# TwinSensorRevC.net
KiCad netlist of a schematic drawn in EAGLE
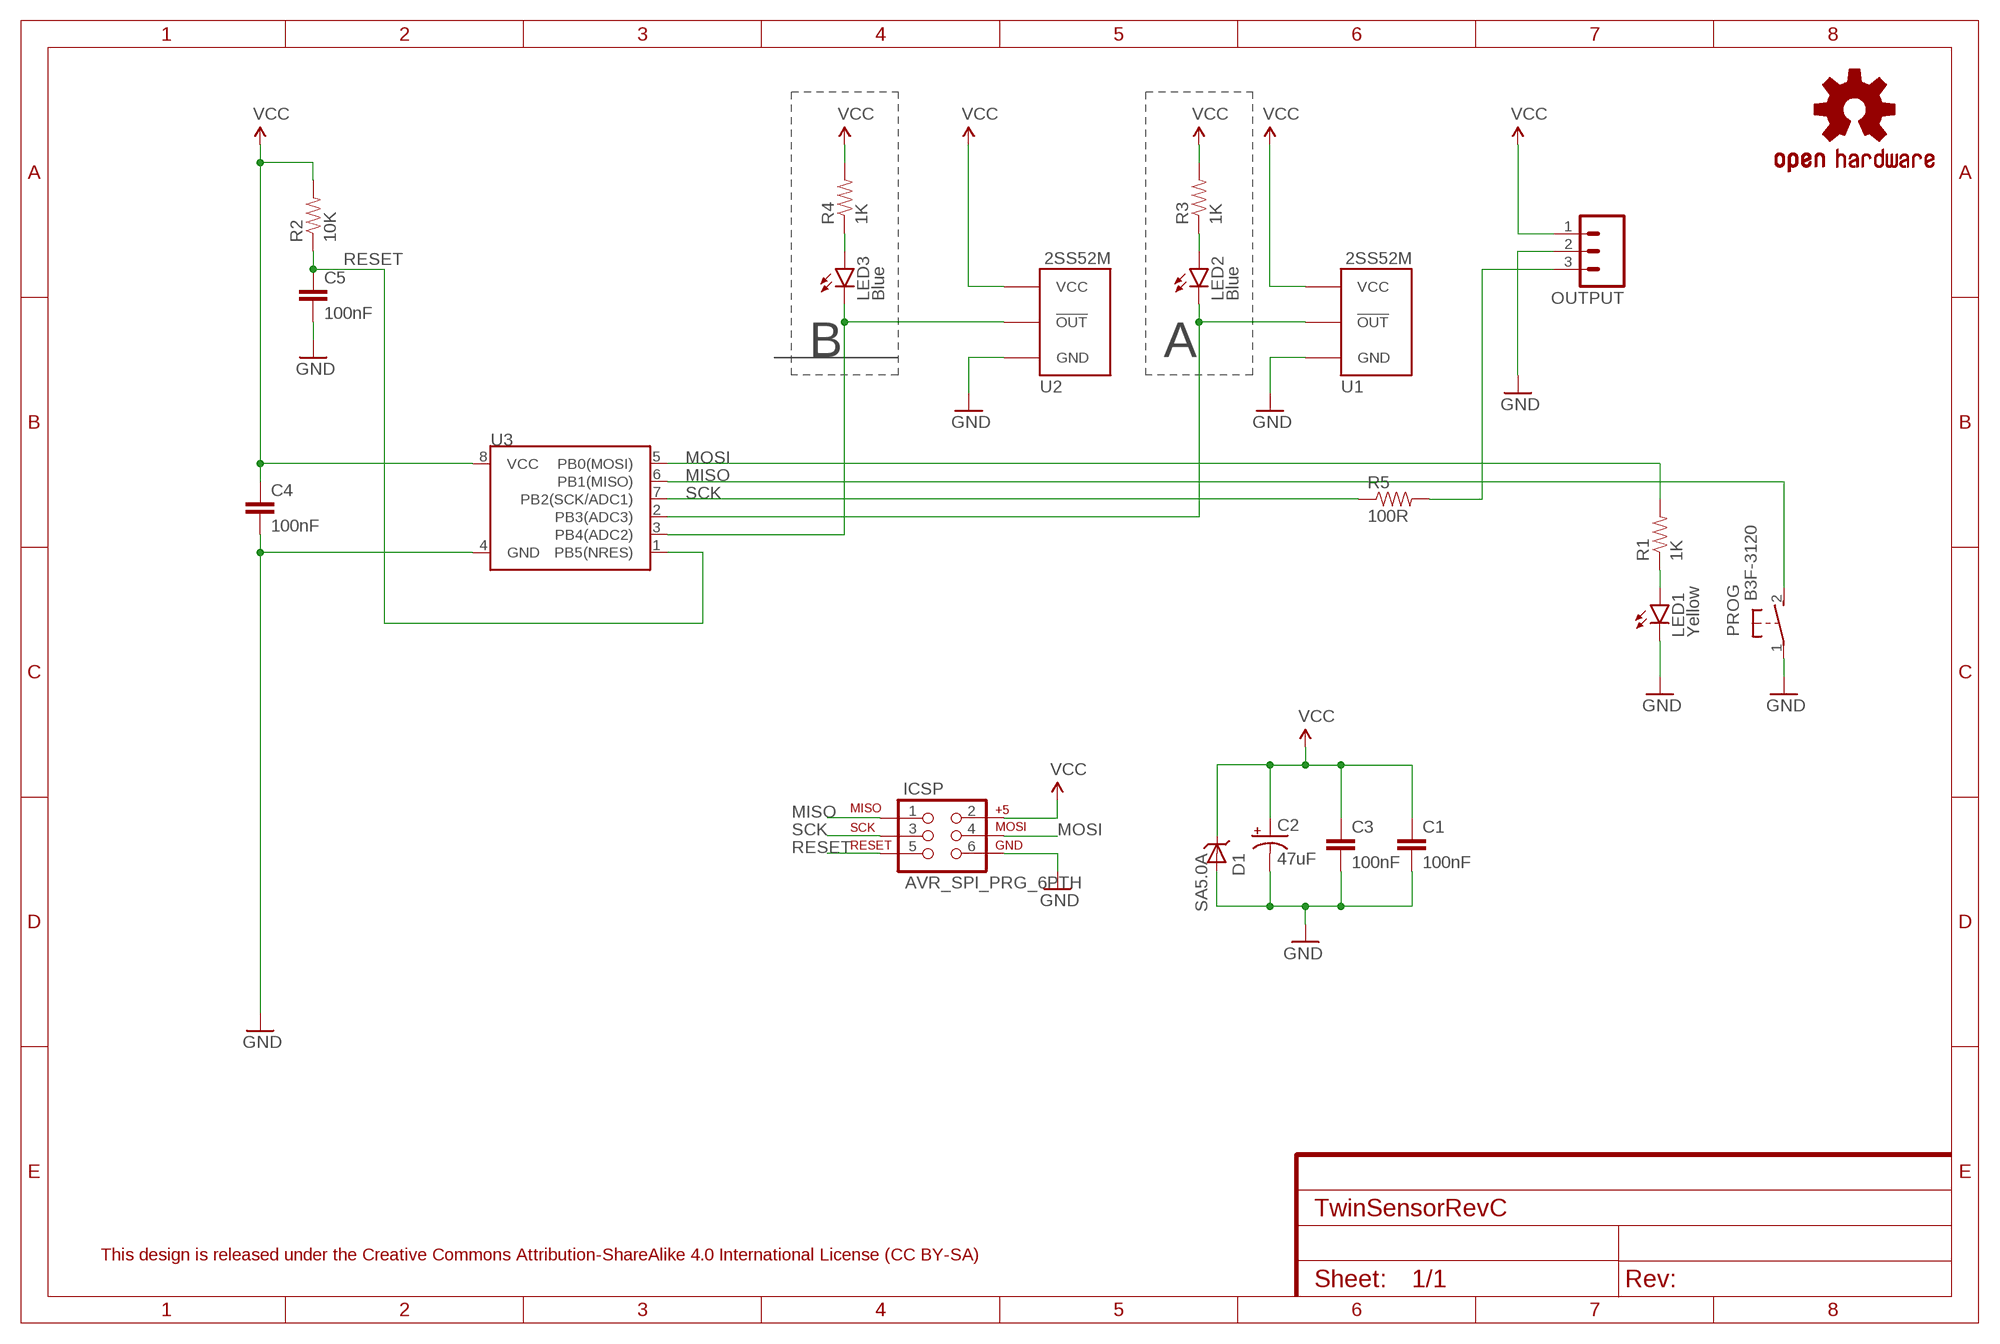
[diagram p0: schematic, sheet 1]

(export (version "E")
  (design (tool "Eeschema 10.0.6"))
  (components
    (comp (ref "C1")
      (value "100nF")
      (footprint "eagle-import:CAP-PTH-SMALL")
      (libsource (lib "eagle-import") (part "CAPPTH"))
    )
    (comp (ref "C2")
      (value "47uF")
      (footprint "eagle-import:CPOL-RADIAL-100UF-25V")
      (libsource (lib "eagle-import") (part "CAP_POLPTH1"))
    )
    (comp (ref "C3")
      (value "100nF")
      (footprint "eagle-import:CAP-PTH-SMALL")
      (libsource (lib "eagle-import") (part "CAPPTH"))
    )
    (comp (ref "C4")
      (value "100nF")
      (footprint "eagle-import:CAP-PTH-SMALL")
      (libsource (lib "eagle-import") (part "CAPPTH"))
    )
    (comp (ref "C5")
      (value "100nF")
      (footprint "eagle-import:CAP-PTH-SMALL")
      (libsource (lib "eagle-import") (part "CAPPTH"))
    )
    (comp (ref "D1")
      (value "SA5.0A")
      (footprint "eagle-import:DO41_TVS_UNI")
      (libsource (lib "eagle-import") (part "SA5.0A"))
    )
    (comp (ref "ICSP")
      (value "AVR_SPI_PRG_6PTH")
      (footprint "eagle-import:2X3")
      (libsource (lib "eagle-import") (part "AVR_SPI_PRG_6PTH"))
    )
    (comp (ref "LED1")
      (value "Yellow")
      (footprint "eagle-import:LED3MM")
      (libsource (lib "eagle-import") (part "LED3MM"))
    )
    (comp (ref "LED2")
      (value "Blue")
      (footprint "eagle-import:LED3MM")
      (libsource (lib "eagle-import") (part "LED3MM"))
    )
    (comp (ref "LED3")
      (value "Blue")
      (footprint "eagle-import:LED3MM")
      (libsource (lib "eagle-import") (part "LED3MM"))
    )
    (comp (ref "LOGO1")
      (value "OSHW-LOGOS")
      (footprint "eagle-import:OSHW-LOGO-S")
      (libsource (lib "eagle-import") (part "OSHW-LOGOS"))
    )
    (comp (ref "OUTPUT")
      (value "M03PTH")
      (footprint "eagle-import:1X03")
      (libsource (lib "eagle-import") (part "M03PTH"))
    )
    (comp (ref "PROG")
      (value "B3F-3120")
      (footprint "eagle-import:B3F-3120")
      (fields (field (name "MPN") "B3F-3100"))
      (libsource (lib "eagle-import") (part "B3F-3120"))
    )
    (comp (ref "R1")
      (value "1K")
      (footprint "eagle-import:AXIAL-0.4")
      (libsource (lib "eagle-import") (part "RESISTORPTH-1/4W"))
    )
    (comp (ref "R2")
      (value "10K")
      (footprint "eagle-import:AXIAL-0.4")
      (libsource (lib "eagle-import") (part "RESISTORPTH-1/4W"))
    )
    (comp (ref "R3")
      (value "1K")
      (footprint "eagle-import:AXIAL-0.4")
      (libsource (lib "eagle-import") (part "RESISTORPTH-1/4W"))
    )
    (comp (ref "R4")
      (value "1K")
      (footprint "eagle-import:AXIAL-0.4")
      (libsource (lib "eagle-import") (part "RESISTORPTH-1/4W"))
    )
    (comp (ref "R5")
      (value "100R")
      (footprint "eagle-import:AXIAL-0.4")
      (libsource (lib "eagle-import") (part "RESISTORPTH-1/4W"))
    )
    (comp (ref "U1")
      (value "2SS52MVERT")
      (footprint "eagle-import:2SS52M_VERT")
      (libsource (lib "eagle-import") (part "2SS52MVERT"))
    )
    (comp (ref "U2")
      (value "2SS52MVERT")
      (footprint "eagle-import:2SS52M_VERT")
      (libsource (lib "eagle-import") (part "2SS52MVERT"))
    )
    (comp (ref "U3")
      (value "ATTINY45DIL08_LONG_PADS")
      (footprint "eagle-import:DIL08")
      (libsource (lib "eagle-import") (part "ATTINY45DIL08_LONG_PADS"))
    )
  )
  (nets
    (net (code "1") (name "/MISO") (class "Default")
      (node (ref "ICSP") (pin "1") (pinfunction "1_1") (pintype "passive"))
      (node (ref "PROG") (pin "2") (pinfunction "S_2") (pintype "passive"))
      (node (ref "U3") (pin "6") (pinfunction "PB1(MISO)_6") (pintype "bidirectional"))
    )
    (net (code "2") (name "/MOSI") (class "Default")
      (node (ref "ICSP") (pin "4") (pinfunction "4_4") (pintype "passive"))
      (node (ref "R1") (pin "P$2") (pinfunction "2_P$2") (pintype "passive"))
      (node (ref "U3") (pin "5") (pinfunction "PB0(MOSI)_5") (pintype "bidirectional"))
    )
    (net (code "3") (name "/RESET") (class "Default")
      (node (ref "C5") (pin "1") (pinfunction "1_1") (pintype "passive"))
      (node (ref "ICSP") (pin "5") (pinfunction "5_5") (pintype "passive"))
      (node (ref "R2") (pin "P$1") (pinfunction "1_P$1") (pintype "passive"))
      (node (ref "U3") (pin "1") (pinfunction "PB5(NRES)_1") (pintype "bidirectional"))
    )
    (net (code "4") (name "/SCK") (class "Default")
      (node (ref "ICSP") (pin "3") (pinfunction "3_3") (pintype "passive"))
      (node (ref "R5") (pin "P$1") (pinfunction "1_P$1") (pintype "passive"))
      (node (ref "U3") (pin "7") (pinfunction "PB2(SCK/ADC1)_7") (pintype "bidirectional"))
    )
    (net (code "5") (name "GND") (class "Default")
      (node (ref "C1") (pin "2") (pinfunction "2_2") (pintype "passive"))
      (node (ref "C2") (pin "2") (pinfunction "-_2") (pintype "passive"))
      (node (ref "C3") (pin "2") (pinfunction "2_2") (pintype "passive"))
      (node (ref "C4") (pin "2") (pinfunction "2_2") (pintype "passive"))
      (node (ref "C5") (pin "2") (pinfunction "2_2") (pintype "passive"))
      (node (ref "D1") (pin "ANODE") (pinfunction "ANODE_ANODE") (pintype "passive"))
      (node (ref "ICSP") (pin "6") (pinfunction "6_6") (pintype "passive"))
      (node (ref "LED1") (pin "K") (pinfunction "C_K") (pintype "passive"))
      (node (ref "OUTPUT") (pin "2") (pinfunction "2_2") (pintype "passive"))
      (node (ref "PROG") (pin "1") (pinfunction "P_1") (pintype "passive"))
      (node (ref "U1") (pin "P$1") (pinfunction "GND_P$1") (pintype "bidirectional"))
      (node (ref "U2") (pin "P$1") (pinfunction "GND_P$1") (pintype "bidirectional"))
      (node (ref "U3") (pin "4") (pinfunction "GND_4") (pintype "bidirectional"))
    )
    (net (code "6") (name "Net-(LED2-C)") (class "Default")
      (node (ref "LED2") (pin "K") (pinfunction "C_K") (pintype "passive"))
      (node (ref "U1") (pin "P$2") (pinfunction "~{OUT}_P$2") (pintype "bidirectional"))
      (node (ref "U3") (pin "2") (pinfunction "PB3(ADC3)_2") (pintype "bidirectional"))
    )
    (net (code "7") (name "Net-(LED3-C)") (class "Default")
      (node (ref "LED3") (pin "K") (pinfunction "C_K") (pintype "passive"))
      (node (ref "U2") (pin "P$2") (pinfunction "~{OUT}_P$2") (pintype "bidirectional"))
      (node (ref "U3") (pin "3") (pinfunction "PB4(ADC2)_3") (pintype "bidirectional"))
    )
    (net (code "8") (name "Net-(R1-1)") (class "Default")
      (node (ref "LED1") (pin "A") (pinfunction "A_A") (pintype "passive"))
      (node (ref "R1") (pin "P$1") (pinfunction "1_P$1") (pintype "passive"))
    )
    (net (code "9") (name "Net-(R3-1)") (class "Default")
      (node (ref "LED2") (pin "A") (pinfunction "A_A") (pintype "passive"))
      (node (ref "R3") (pin "P$1") (pinfunction "1_P$1") (pintype "passive"))
    )
    (net (code "10") (name "Net-(R4-1)") (class "Default")
      (node (ref "LED3") (pin "A") (pinfunction "A_A") (pintype "passive"))
      (node (ref "R4") (pin "P$1") (pinfunction "1_P$1") (pintype "passive"))
    )
    (net (code "11") (name "Net-(R5-2)") (class "Default")
      (node (ref "OUTPUT") (pin "3") (pinfunction "3_3") (pintype "passive"))
      (node (ref "R5") (pin "P$2") (pinfunction "2_P$2") (pintype "passive"))
    )
    (net (code "12") (name "VCC") (class "Default")
      (node (ref "C1") (pin "1") (pinfunction "1_1") (pintype "passive"))
      (node (ref "C2") (pin "1") (pinfunction "+_1") (pintype "passive"))
      (node (ref "C3") (pin "1") (pinfunction "1_1") (pintype "passive"))
      (node (ref "C4") (pin "1") (pinfunction "1_1") (pintype "passive"))
      (node (ref "D1") (pin "CATHODE") (pinfunction "CATHODE_CATHODE") (pintype "passive"))
      (node (ref "ICSP") (pin "2") (pinfunction "2_2") (pintype "passive"))
      (node (ref "OUTPUT") (pin "1") (pinfunction "1_1") (pintype "passive"))
      (node (ref "R2") (pin "P$2") (pinfunction "2_P$2") (pintype "passive"))
      (node (ref "R3") (pin "P$2") (pinfunction "2_P$2") (pintype "passive"))
      (node (ref "R4") (pin "P$2") (pinfunction "2_P$2") (pintype "passive"))
      (node (ref "U1") (pin "P$3") (pinfunction "VCC_P$3") (pintype "bidirectional"))
      (node (ref "U2") (pin "P$3") (pinfunction "VCC_P$3") (pintype "bidirectional"))
      (node (ref "U3") (pin "8") (pinfunction "VCC_8") (pintype "bidirectional"))
    )
  )
)
